# 19_RAM_Memory_module.net
KiCad netlist of a schematic drawn in Altium Designer
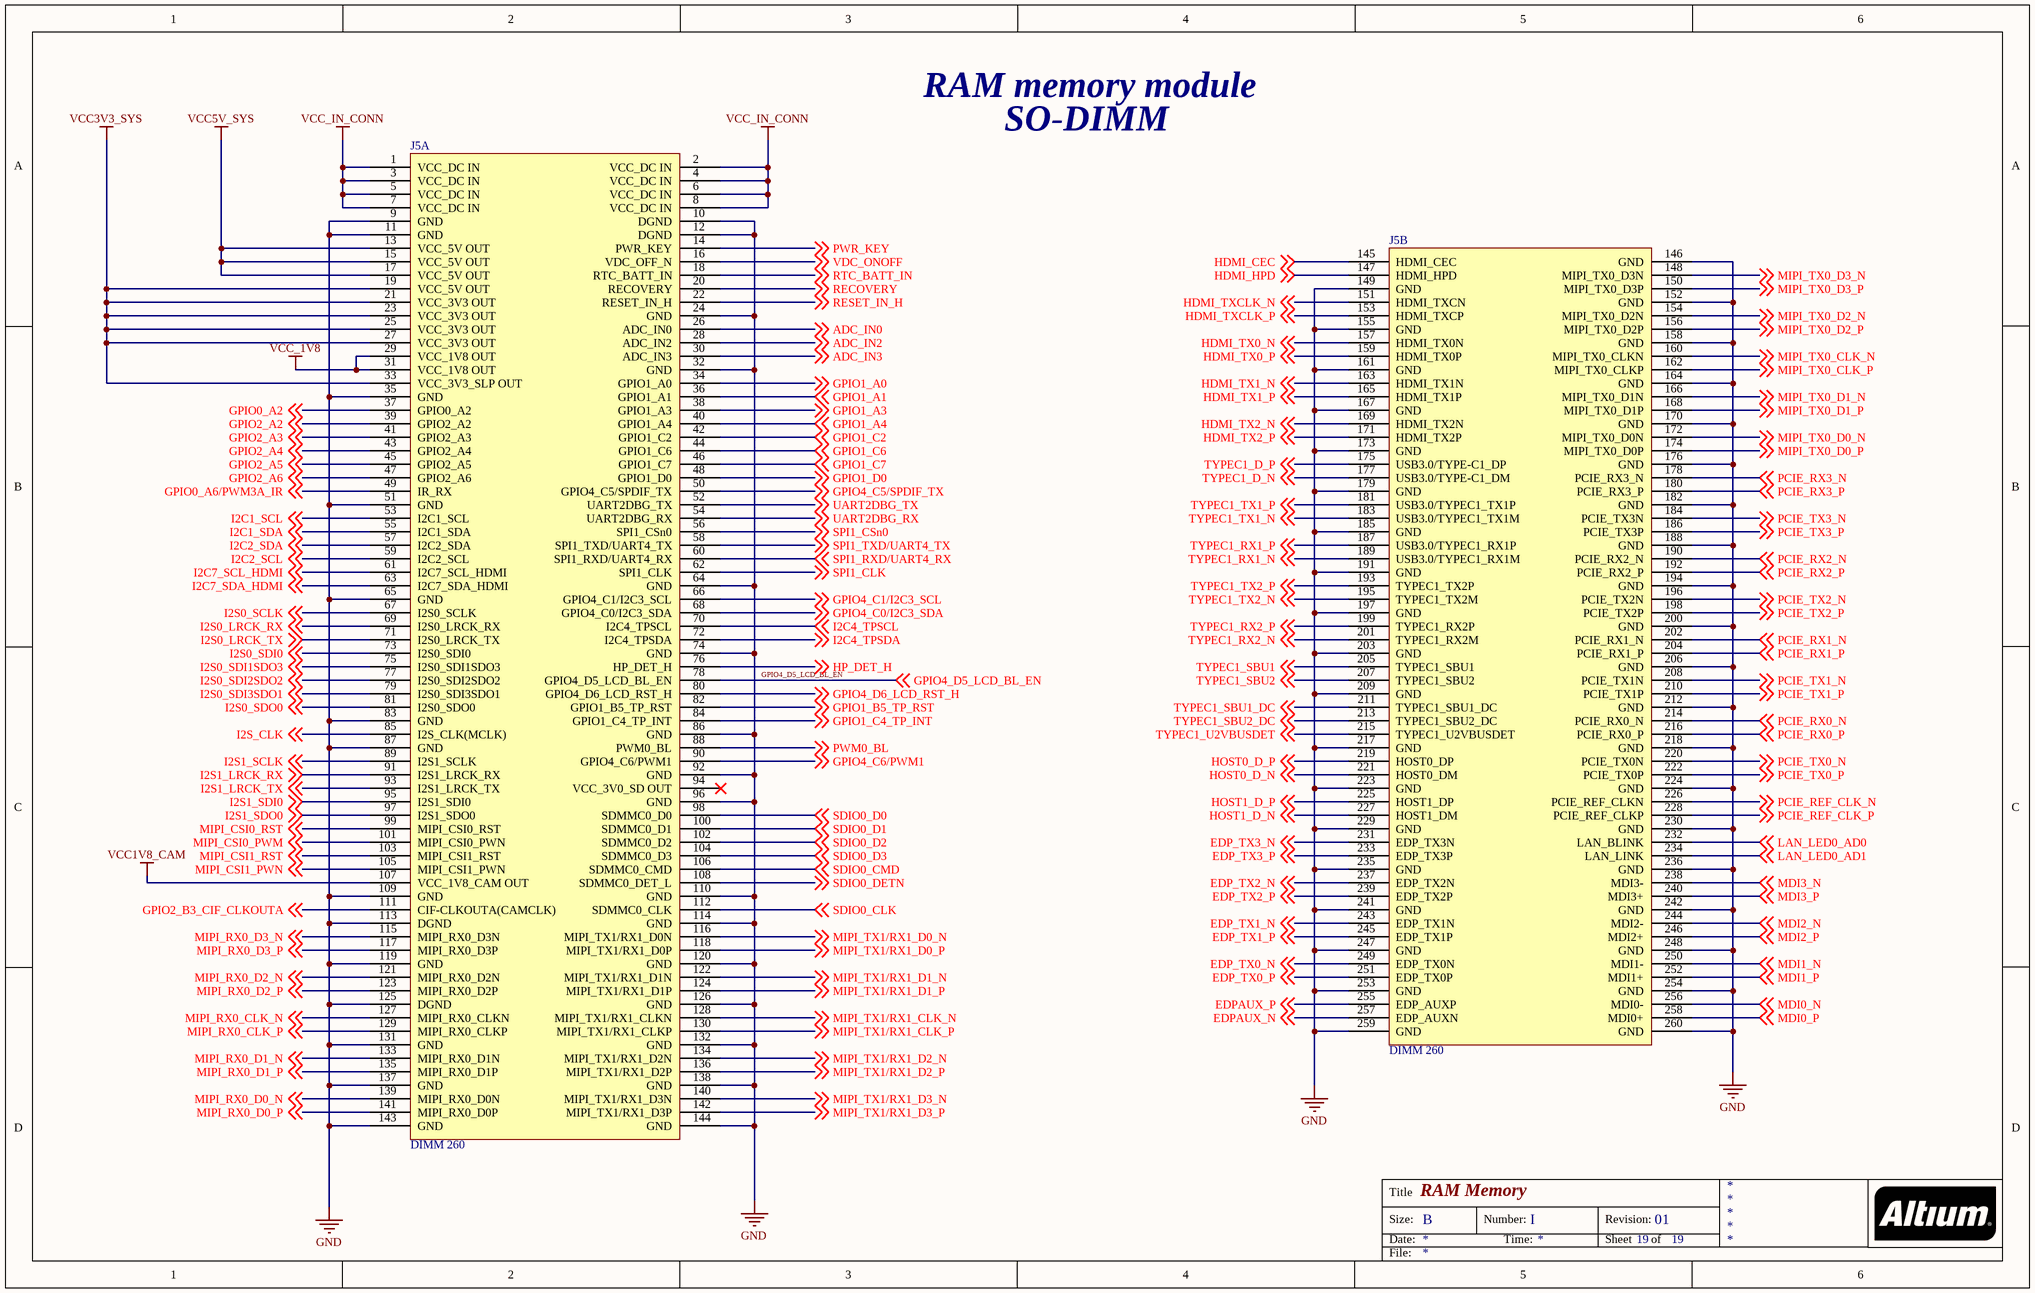
[diagram p0: [19] RAM Memory module.SchDoc]

(export (version "E")
  (design (tool "Eeschema 10.0.6"))
  (components
    (comp (ref "J5")
      (value "DIMM 260")
      (footprint "DIMM260_DDR4")
      (description "Dimm 260 pin smd plating on pcb")
      (fields (field (name "MANUFACTURER") "NA"))
      (libsource (lib "EsteemPCB_SOM_Course_intlib") (part "CON-DIMM_260-SMD"))
    )
  )
  (nets
    (net (code "1") (name "ADC_IN0") (class "Default")
      (node (ref "J5") (pin "26") (pinfunction "ADC_IN0_26") (pintype "passive"))
    )
    (net (code "2") (name "ADC_IN2") (class "Default")
      (node (ref "J5") (pin "28") (pinfunction "ADC_IN2_28") (pintype "passive"))
    )
    (net (code "3") (name "ADC_IN3") (class "Default")
      (node (ref "J5") (pin "30") (pinfunction "ADC_IN3_30") (pintype "passive"))
    )
    (net (code "4") (name "EDPAUX_N") (class "Default")
      (node (ref "J5") (pin "257") (pinfunction "EDP_AUXN_257") (pintype "passive"))
    )
    (net (code "5") (name "EDPAUX_P") (class "Default")
      (node (ref "J5") (pin "255") (pinfunction "EDP_AUXP_255") (pintype "passive"))
    )
    (net (code "6") (name "EDP_TX0_N") (class "Default")
      (node (ref "J5") (pin "249") (pinfunction "EDP_TX0N_249") (pintype "passive"))
    )
    (net (code "7") (name "EDP_TX0_P") (class "Default")
      (node (ref "J5") (pin "251") (pinfunction "EDP_TX0P_251") (pintype "passive"))
    )
    (net (code "8") (name "EDP_TX1_N") (class "Default")
      (node (ref "J5") (pin "243") (pinfunction "EDP_TX1N_243") (pintype "passive"))
    )
    (net (code "9") (name "EDP_TX1_P") (class "Default")
      (node (ref "J5") (pin "245") (pinfunction "EDP_TX1P_245") (pintype "passive"))
    )
    (net (code "10") (name "EDP_TX2_N") (class "Default")
      (node (ref "J5") (pin "237") (pinfunction "EDP_TX2N_237") (pintype "passive"))
    )
    (net (code "11") (name "EDP_TX2_P") (class "Default")
      (node (ref "J5") (pin "239") (pinfunction "EDP_TX2P_239") (pintype "passive"))
    )
    (net (code "12") (name "EDP_TX3_N") (class "Default")
      (node (ref "J5") (pin "231") (pinfunction "EDP_TX3N_231") (pintype "passive"))
    )
    (net (code "13") (name "EDP_TX3_P") (class "Default")
      (node (ref "J5") (pin "233") (pinfunction "EDP_TX3P_233") (pintype "passive"))
    )
    (net (code "14") (name "GND") (class "Default")
      (node (ref "J5") (pin "10") (pinfunction "DGND_10") (pintype "passive"))
      (node (ref "J5") (pin "109") (pinfunction "GND_109") (pintype "passive"))
      (node (ref "J5") (pin "11") (pinfunction "GND_11") (pintype "passive"))
      (node (ref "J5") (pin "110") (pinfunction "GND_110") (pintype "passive"))
      (node (ref "J5") (pin "113") (pinfunction "DGND_113") (pintype "passive"))
      (node (ref "J5") (pin "114") (pinfunction "GND_114") (pintype "passive"))
      (node (ref "J5") (pin "119") (pinfunction "GND_119") (pintype "passive"))
      (node (ref "J5") (pin "12") (pinfunction "DGND_12") (pintype "passive"))
      (node (ref "J5") (pin "120") (pinfunction "GND_120") (pintype "passive"))
      (node (ref "J5") (pin "125") (pinfunction "DGND_125") (pintype "passive"))
      (node (ref "J5") (pin "126") (pinfunction "GND_126") (pintype "passive"))
      (node (ref "J5") (pin "131") (pinfunction "GND_131") (pintype "passive"))
      (node (ref "J5") (pin "132") (pinfunction "GND_132") (pintype "passive"))
      (node (ref "J5") (pin "137") (pinfunction "GND_137") (pintype "passive"))
      (node (ref "J5") (pin "138") (pinfunction "GND_138") (pintype "passive"))
      (node (ref "J5") (pin "143") (pinfunction "GND_143") (pintype "passive"))
      (node (ref "J5") (pin "144") (pinfunction "GND_144") (pintype "passive"))
      (node (ref "J5") (pin "146") (pinfunction "GND_146") (pintype "passive"))
      (node (ref "J5") (pin "149") (pinfunction "GND_149") (pintype "passive"))
      (node (ref "J5") (pin "152") (pinfunction "GND_152") (pintype "passive"))
      (node (ref "J5") (pin "155") (pinfunction "GND_155") (pintype "passive"))
      (node (ref "J5") (pin "158") (pinfunction "GND_158") (pintype "passive"))
      (node (ref "J5") (pin "161") (pinfunction "GND_161") (pintype "passive"))
      (node (ref "J5") (pin "164") (pinfunction "GND_164") (pintype "passive"))
      (node (ref "J5") (pin "167") (pinfunction "GND_167") (pintype "passive"))
      (node (ref "J5") (pin "170") (pinfunction "GND_170") (pintype "passive"))
      (node (ref "J5") (pin "173") (pinfunction "GND_173") (pintype "passive"))
      (node (ref "J5") (pin "176") (pinfunction "GND_176") (pintype "passive"))
      (node (ref "J5") (pin "179") (pinfunction "GND_179") (pintype "passive"))
      (node (ref "J5") (pin "182") (pinfunction "GND_182") (pintype "passive"))
      (node (ref "J5") (pin "185") (pinfunction "GND_185") (pintype "passive"))
      (node (ref "J5") (pin "188") (pinfunction "GND_188") (pintype "passive"))
      (node (ref "J5") (pin "191") (pinfunction "GND_191") (pintype "passive"))
      (node (ref "J5") (pin "194") (pinfunction "GND_194") (pintype "passive"))
      (node (ref "J5") (pin "197") (pinfunction "GND_197") (pintype "passive"))
      (node (ref "J5") (pin "200") (pinfunction "GND_200") (pintype "passive"))
      (node (ref "J5") (pin "203") (pinfunction "GND_203") (pintype "passive"))
      (node (ref "J5") (pin "206") (pinfunction "GND_206") (pintype "passive"))
      (node (ref "J5") (pin "209") (pinfunction "GND_209") (pintype "passive"))
      (node (ref "J5") (pin "212") (pinfunction "GND_212") (pintype "passive"))
      (node (ref "J5") (pin "217") (pinfunction "GND_217") (pintype "passive"))
      (node (ref "J5") (pin "218") (pinfunction "GND_218") (pintype "passive"))
      (node (ref "J5") (pin "223") (pinfunction "GND_223") (pintype "passive"))
      (node (ref "J5") (pin "224") (pinfunction "GND_224") (pintype "passive"))
      (node (ref "J5") (pin "229") (pinfunction "GND_229") (pintype "passive"))
      (node (ref "J5") (pin "230") (pinfunction "GND_230") (pintype "passive"))
      (node (ref "J5") (pin "235") (pinfunction "GND_235") (pintype "passive"))
      (node (ref "J5") (pin "236") (pinfunction "GND_236") (pintype "passive"))
      (node (ref "J5") (pin "24") (pinfunction "GND_24") (pintype "passive"))
      (node (ref "J5") (pin "241") (pinfunction "GND_241") (pintype "passive"))
      (node (ref "J5") (pin "242") (pinfunction "GND_242") (pintype "passive"))
      (node (ref "J5") (pin "247") (pinfunction "GND_247") (pintype "passive"))
      (node (ref "J5") (pin "248") (pinfunction "GND_248") (pintype "passive"))
      (node (ref "J5") (pin "253") (pinfunction "GND_253") (pintype "passive"))
      (node (ref "J5") (pin "254") (pinfunction "GND_254") (pintype "passive"))
      (node (ref "J5") (pin "259") (pinfunction "GND_259") (pintype "passive"))
      (node (ref "J5") (pin "260") (pinfunction "GND_260") (pintype "passive"))
      (node (ref "J5") (pin "32") (pinfunction "GND_32") (pintype "passive"))
      (node (ref "J5") (pin "35") (pinfunction "GND_35") (pintype "passive"))
      (node (ref "J5") (pin "51") (pinfunction "GND_51") (pintype "passive"))
      (node (ref "J5") (pin "64") (pinfunction "GND_64") (pintype "passive"))
      (node (ref "J5") (pin "65") (pinfunction "GND_65") (pintype "passive"))
      (node (ref "J5") (pin "74") (pinfunction "GND_74") (pintype "passive"))
      (node (ref "J5") (pin "83") (pinfunction "GND_83") (pintype "passive"))
      (node (ref "J5") (pin "86") (pinfunction "GND_86") (pintype "passive"))
      (node (ref "J5") (pin "87") (pinfunction "GND_87") (pintype "passive"))
      (node (ref "J5") (pin "9") (pinfunction "GND_9") (pintype "passive"))
      (node (ref "J5") (pin "92") (pinfunction "GND_92") (pintype "passive"))
      (node (ref "J5") (pin "96") (pinfunction "GND_96") (pintype "passive"))
    )
    (net (code "15") (name "GPIO0_A2") (class "Default")
      (node (ref "J5") (pin "37") (pinfunction "GPIO0_A2_37") (pintype "passive"))
    )
    (net (code "16") (name "GPIO0_A6{slash}PWM3A_IR") (class "Default")
      (node (ref "J5") (pin "49") (pinfunction "IR_RX_49") (pintype "passive"))
    )
    (net (code "17") (name "GPIO1_A0") (class "Default")
      (node (ref "J5") (pin "34") (pinfunction "GPIO1_A0_34") (pintype "passive"))
    )
    (net (code "18") (name "GPIO1_A1") (class "Default")
      (node (ref "J5") (pin "36") (pinfunction "GPIO1_A1_36") (pintype "passive"))
    )
    (net (code "19") (name "GPIO1_A3") (class "Default")
      (node (ref "J5") (pin "38") (pinfunction "GPIO1_A3_38") (pintype "passive"))
    )
    (net (code "20") (name "GPIO1_A4") (class "Default")
      (node (ref "J5") (pin "40") (pinfunction "GPIO1_A4_40") (pintype "passive"))
    )
    (net (code "21") (name "GPIO1_B5_TP_RST") (class "Default")
      (node (ref "J5") (pin "82") (pinfunction "GPIO1_B5_TP_RST_82") (pintype "passive"))
    )
    (net (code "22") (name "GPIO1_C2") (class "Default")
      (node (ref "J5") (pin "42") (pinfunction "GPIO1_C2_42") (pintype "passive"))
    )
    (net (code "23") (name "GPIO1_C4_TP_INT") (class "Default")
      (node (ref "J5") (pin "84") (pinfunction "GPIO1_C4_TP_INT_84") (pintype "passive"))
    )
    (net (code "24") (name "GPIO1_C6") (class "Default")
      (node (ref "J5") (pin "44") (pinfunction "GPIO1_C6_44") (pintype "passive"))
    )
    (net (code "25") (name "GPIO1_C7") (class "Default")
      (node (ref "J5") (pin "46") (pinfunction "GPIO1_C7_46") (pintype "passive"))
    )
    (net (code "26") (name "GPIO1_D0") (class "Default")
      (node (ref "J5") (pin "48") (pinfunction "GPIO1_D0_48") (pintype "passive"))
    )
    (net (code "27") (name "GPIO2_A2") (class "Default")
      (node (ref "J5") (pin "39") (pinfunction "GPIO2_A2_39") (pintype "passive"))
    )
    (net (code "28") (name "GPIO2_A3") (class "Default")
      (node (ref "J5") (pin "41") (pinfunction "GPIO2_A3_41") (pintype "passive"))
    )
    (net (code "29") (name "GPIO2_A4") (class "Default")
      (node (ref "J5") (pin "43") (pinfunction "GPIO2_A4_43") (pintype "passive"))
    )
    (net (code "30") (name "GPIO2_A5") (class "Default")
      (node (ref "J5") (pin "45") (pinfunction "GPIO2_A5_45") (pintype "passive"))
    )
    (net (code "31") (name "GPIO2_A6") (class "Default")
      (node (ref "J5") (pin "47") (pinfunction "GPIO2_A6_47") (pintype "passive"))
    )
    (net (code "32") (name "GPIO2_B3_CIF_CLKOUTA") (class "Default")
      (node (ref "J5") (pin "111") (pinfunction "CIF-CLKOUTA(CAMCLK)_111") (pintype "passive"))
    )
    (net (code "33") (name "GPIO4_C0{slash}I2C3_SDA") (class "Default")
      (node (ref "J5") (pin "68") (pinfunction "GPIO4_C0/I2C3_SDA_68") (pintype "passive"))
    )
    (net (code "34") (name "GPIO4_C1{slash}I2C3_SCL") (class "Default")
      (node (ref "J5") (pin "66") (pinfunction "GPIO4_C1/I2C3_SCL_66") (pintype "passive"))
    )
    (net (code "35") (name "GPIO4_C5{slash}SPDIF_TX") (class "Default")
      (node (ref "J5") (pin "50") (pinfunction "GPIO4_C5/SPDIF_TX_50") (pintype "passive"))
    )
    (net (code "36") (name "GPIO4_C6{slash}PWM1") (class "Default")
      (node (ref "J5") (pin "90") (pinfunction "GPIO4_C6/PWM1_90") (pintype "passive"))
    )
    (net (code "37") (name "GPIO4_D5_LCD_BL_EN") (class "Default")
      (node (ref "J5") (pin "78") (pinfunction "GPIO4_D5_LCD_BL_EN_78") (pintype "passive"))
    )
    (net (code "38") (name "GPIO4_D6_LCD_RST_H") (class "Default")
      (node (ref "J5") (pin "80") (pinfunction "GPIO4_D6_LCD_RST_H_80") (pintype "passive"))
    )
    (net (code "39") (name "HDMI_CEC") (class "Default")
      (node (ref "J5") (pin "145") (pinfunction "HDMI_CEC_145") (pintype "passive"))
    )
    (net (code "40") (name "HDMI_HPD") (class "Default")
      (node (ref "J5") (pin "147") (pinfunction "HDMI_HPD_147") (pintype "passive"))
    )
    (net (code "41") (name "HDMI_TX0_N") (class "Default")
      (node (ref "J5") (pin "157") (pinfunction "HDMI_TX0N_157") (pintype "passive"))
    )
    (net (code "42") (name "HDMI_TX0_P") (class "Default")
      (node (ref "J5") (pin "159") (pinfunction "HDMI_TX0P_159") (pintype "passive"))
    )
    (net (code "43") (name "HDMI_TX1_N") (class "Default")
      (node (ref "J5") (pin "163") (pinfunction "HDMI_TX1N_163") (pintype "passive"))
    )
    (net (code "44") (name "HDMI_TX1_P") (class "Default")
      (node (ref "J5") (pin "165") (pinfunction "HDMI_TX1P_165") (pintype "passive"))
    )
    (net (code "45") (name "HDMI_TX2_N") (class "Default")
      (node (ref "J5") (pin "169") (pinfunction "HDMI_TX2N_169") (pintype "passive"))
    )
    (net (code "46") (name "HDMI_TX2_P") (class "Default")
      (node (ref "J5") (pin "171") (pinfunction "HDMI_TX2P_171") (pintype "passive"))
    )
    (net (code "47") (name "HDMI_TXCLK_N") (class "Default")
      (node (ref "J5") (pin "151") (pinfunction "HDMI_TXCN_151") (pintype "passive"))
    )
    (net (code "48") (name "HDMI_TXCLK_P") (class "Default")
      (node (ref "J5") (pin "153") (pinfunction "HDMI_TXCP_153") (pintype "passive"))
    )
    (net (code "49") (name "HOST0_D_N") (class "Default")
      (node (ref "J5") (pin "221") (pinfunction "HOST0_DM_221") (pintype "passive"))
    )
    (net (code "50") (name "HOST0_D_P") (class "Default")
      (node (ref "J5") (pin "219") (pinfunction "HOST0_DP_219") (pintype "passive"))
    )
    (net (code "51") (name "HOST1_D_N") (class "Default")
      (node (ref "J5") (pin "227") (pinfunction "HOST1_DM_227") (pintype "passive"))
    )
    (net (code "52") (name "HOST1_D_P") (class "Default")
      (node (ref "J5") (pin "225") (pinfunction "HOST1_DP_225") (pintype "passive"))
    )
    (net (code "53") (name "HP_DET_H") (class "Default")
      (node (ref "J5") (pin "76") (pinfunction "HP_DET_H_76") (pintype "passive"))
    )
    (net (code "54") (name "I2C1_SCL") (class "Default")
      (node (ref "J5") (pin "53") (pinfunction "I2C1_SCL_53") (pintype "passive"))
    )
    (net (code "55") (name "I2C1_SDA") (class "Default")
      (node (ref "J5") (pin "55") (pinfunction "I2C1_SDA_55") (pintype "passive"))
    )
    (net (code "56") (name "I2C2_SCL") (class "Default")
      (node (ref "J5") (pin "59") (pinfunction "I2C2_SCL_59") (pintype "passive"))
    )
    (net (code "57") (name "I2C2_SDA") (class "Default")
      (node (ref "J5") (pin "57") (pinfunction "I2C2_SDA_57") (pintype "passive"))
    )
    (net (code "58") (name "I2C4_TPSCL") (class "Default")
      (node (ref "J5") (pin "70") (pinfunction "I2C4_TPSCL_70") (pintype "passive"))
    )
    (net (code "59") (name "I2C4_TPSDA") (class "Default")
      (node (ref "J5") (pin "72") (pinfunction "I2C4_TPSDA_72") (pintype "passive"))
    )
    (net (code "60") (name "I2C7_SCL_HDMI") (class "Default")
      (node (ref "J5") (pin "61") (pinfunction "I2C7_SCL_HDMI_61") (pintype "passive"))
    )
    (net (code "61") (name "I2C7_SDA_HDMI") (class "Default")
      (node (ref "J5") (pin "63") (pinfunction "I2C7_SDA_HDMI_63") (pintype "passive"))
    )
    (net (code "62") (name "I2S0_LRCK_RX") (class "Default")
      (node (ref "J5") (pin "69") (pinfunction "I2S0_LRCK_RX_69") (pintype "passive"))
    )
    (net (code "63") (name "I2S0_LRCK_TX") (class "Default")
      (node (ref "J5") (pin "71") (pinfunction "I2S0_LRCK_TX_71") (pintype "passive"))
    )
    (net (code "64") (name "I2S0_SCLK") (class "Default")
      (node (ref "J5") (pin "67") (pinfunction "I2S0_SCLK_67") (pintype "passive"))
    )
    (net (code "65") (name "I2S0_SDI0") (class "Default")
      (node (ref "J5") (pin "73") (pinfunction "I2S0_SDI0_73") (pintype "passive"))
    )
    (net (code "66") (name "I2S0_SDI1SDO3") (class "Default")
      (node (ref "J5") (pin "75") (pinfunction "I2S0_SDI1SDO3_75") (pintype "passive"))
    )
    (net (code "67") (name "I2S0_SDI2SDO2") (class "Default")
      (node (ref "J5") (pin "77") (pinfunction "I2S0_SDI2SDO2_77") (pintype "passive"))
    )
    (net (code "68") (name "I2S0_SDI3SDO1") (class "Default")
      (node (ref "J5") (pin "79") (pinfunction "I2S0_SDI3SDO1_79") (pintype "passive"))
    )
    (net (code "69") (name "I2S0_SDO0") (class "Default")
      (node (ref "J5") (pin "81") (pinfunction "I2S0_SDO0_81") (pintype "passive"))
    )
    (net (code "70") (name "I2S1_LRCK_RX") (class "Default")
      (node (ref "J5") (pin "91") (pinfunction "I2S1_LRCK_RX_91") (pintype "passive"))
    )
    (net (code "71") (name "I2S1_LRCK_TX") (class "Default")
      (node (ref "J5") (pin "93") (pinfunction "I2S1_LRCK_TX_93") (pintype "passive"))
    )
    (net (code "72") (name "I2S1_SCLK") (class "Default")
      (node (ref "J5") (pin "89") (pinfunction "I2S1_SCLK_89") (pintype "passive"))
    )
    (net (code "73") (name "I2S1_SDI0") (class "Default")
      (node (ref "J5") (pin "95") (pinfunction "I2S1_SDI0_95") (pintype "passive"))
    )
    (net (code "74") (name "I2S1_SDO0") (class "Default")
      (node (ref "J5") (pin "97") (pinfunction "I2S1_SDO0_97") (pintype "passive"))
    )
    (net (code "75") (name "I2S_CLK") (class "Default")
      (node (ref "J5") (pin "85") (pinfunction "I2S_CLK(MCLK)_85") (pintype "passive"))
    )
    (net (code "76") (name "LAN_LED0_AD0") (class "Default")
      (node (ref "J5") (pin "232") (pinfunction "LAN_BLINK_232") (pintype "passive"))
    )
    (net (code "77") (name "LAN_LED0_AD1") (class "Default")
      (node (ref "J5") (pin "234") (pinfunction "LAN_LINK_234") (pintype "passive"))
    )
    (net (code "78") (name "MDI0_N") (class "Default")
      (node (ref "J5") (pin "256") (pinfunction "MDI0-_256") (pintype "passive"))
    )
    (net (code "79") (name "MDI0_P") (class "Default")
      (node (ref "J5") (pin "258") (pinfunction "MDI0+_258") (pintype "passive"))
    )
    (net (code "80") (name "MDI1_N") (class "Default")
      (node (ref "J5") (pin "250") (pinfunction "MDI1-_250") (pintype "passive"))
    )
    (net (code "81") (name "MDI1_P") (class "Default")
      (node (ref "J5") (pin "252") (pinfunction "MDI1+_252") (pintype "passive"))
    )
    (net (code "82") (name "MDI2_N") (class "Default")
      (node (ref "J5") (pin "244") (pinfunction "MDI2-_244") (pintype "passive"))
    )
    (net (code "83") (name "MDI2_P") (class "Default")
      (node (ref "J5") (pin "246") (pinfunction "MDI2+_246") (pintype "passive"))
    )
    (net (code "84") (name "MDI3_N") (class "Default")
      (node (ref "J5") (pin "238") (pinfunction "MDI3-_238") (pintype "passive"))
    )
    (net (code "85") (name "MDI3_P") (class "Default")
      (node (ref "J5") (pin "240") (pinfunction "MDI3+_240") (pintype "passive"))
    )
    (net (code "86") (name "MIPI_CSI0_PWM") (class "Default")
      (node (ref "J5") (pin "101") (pinfunction "MIPI_CSI0_PWN_101") (pintype "passive"))
    )
    (net (code "87") (name "MIPI_CSI0_RST") (class "Default")
      (node (ref "J5") (pin "99") (pinfunction "MIPI_CSI0_RST_99") (pintype "passive"))
    )
    (net (code "88") (name "MIPI_CSI1_PWN") (class "Default")
      (node (ref "J5") (pin "105") (pinfunction "MIPI_CSI1_PWN_105") (pintype "passive"))
    )
    (net (code "89") (name "MIPI_CSI1_RST") (class "Default")
      (node (ref "J5") (pin "103") (pinfunction "MIPI_CSI1_RST_103") (pintype "passive"))
    )
    (net (code "90") (name "MIPI_RX0_CLK_N") (class "Default")
      (node (ref "J5") (pin "127") (pinfunction "MIPI_RX0_CLKN_127") (pintype "passive"))
    )
    (net (code "91") (name "MIPI_RX0_CLK_P") (class "Default")
      (node (ref "J5") (pin "129") (pinfunction "MIPI_RX0_CLKP_129") (pintype "passive"))
    )
    (net (code "92") (name "MIPI_RX0_D0_N") (class "Default")
      (node (ref "J5") (pin "139") (pinfunction "MIPI_RX0_D0N_139") (pintype "passive"))
    )
    (net (code "93") (name "MIPI_RX0_D0_P") (class "Default")
      (node (ref "J5") (pin "141") (pinfunction "MIPI_RX0_D0P_141") (pintype "passive"))
    )
    (net (code "94") (name "MIPI_RX0_D1_N") (class "Default")
      (node (ref "J5") (pin "133") (pinfunction "MIPI_RX0_D1N_133") (pintype "passive"))
    )
    (net (code "95") (name "MIPI_RX0_D1_P") (class "Default")
      (node (ref "J5") (pin "135") (pinfunction "MIPI_RX0_D1P_135") (pintype "passive"))
    )
    (net (code "96") (name "MIPI_RX0_D2_N") (class "Default")
      (node (ref "J5") (pin "121") (pinfunction "MIPI_RX0_D2N_121") (pintype "passive"))
    )
    (net (code "97") (name "MIPI_RX0_D2_P") (class "Default")
      (node (ref "J5") (pin "123") (pinfunction "MIPI_RX0_D2P_123") (pintype "passive"))
    )
    (net (code "98") (name "MIPI_RX0_D3_N") (class "Default")
      (node (ref "J5") (pin "115") (pinfunction "MIPI_RX0_D3N_115") (pintype "passive"))
    )
    (net (code "99") (name "MIPI_RX0_D3_P") (class "Default")
      (node (ref "J5") (pin "117") (pinfunction "MIPI_RX0_D3P_117") (pintype "passive"))
    )
    (net (code "100") (name "MIPI_TX0_CLK_N") (class "Default")
      (node (ref "J5") (pin "160") (pinfunction "MIPI_TX0_CLKN_160") (pintype "passive"))
    )
    (net (code "101") (name "MIPI_TX0_CLK_P") (class "Default")
      (node (ref "J5") (pin "162") (pinfunction "MIPI_TX0_CLKP_162") (pintype "passive"))
    )
    (net (code "102") (name "MIPI_TX0_D0_N") (class "Default")
      (node (ref "J5") (pin "172") (pinfunction "MIPI_TX0_D0N_172") (pintype "passive"))
    )
    (net (code "103") (name "MIPI_TX0_D0_P") (class "Default")
      (node (ref "J5") (pin "174") (pinfunction "MIPI_TX0_D0P_174") (pintype "passive"))
    )
    (net (code "104") (name "MIPI_TX0_D1_N") (class "Default")
      (node (ref "J5") (pin "166") (pinfunction "MIPI_TX0_D1N_166") (pintype "passive"))
    )
    (net (code "105") (name "MIPI_TX0_D1_P") (class "Default")
      (node (ref "J5") (pin "168") (pinfunction "MIPI_TX0_D1P_168") (pintype "passive"))
    )
    (net (code "106") (name "MIPI_TX0_D2_N") (class "Default")
      (node (ref "J5") (pin "154") (pinfunction "MIPI_TX0_D2N_154") (pintype "passive"))
    )
    (net (code "107") (name "MIPI_TX0_D2_P") (class "Default")
      (node (ref "J5") (pin "156") (pinfunction "MIPI_TX0_D2P_156") (pintype "passive"))
    )
    (net (code "108") (name "MIPI_TX0_D3_N") (class "Default")
      (node (ref "J5") (pin "148") (pinfunction "MIPI_TX0_D3N_148") (pintype "passive"))
    )
    (net (code "109") (name "MIPI_TX0_D3_P") (class "Default")
      (node (ref "J5") (pin "150") (pinfunction "MIPI_TX0_D3P_150") (pintype "passive"))
    )
    (net (code "110") (name "MIPI_TX1{slash}RX1_CLK_N") (class "Default")
      (node (ref "J5") (pin "128") (pinfunction "MIPI_TX1/RX1_CLKN_128") (pintype "passive"))
    )
    (net (code "111") (name "MIPI_TX1{slash}RX1_CLK_P") (class "Default")
      (node (ref "J5") (pin "130") (pinfunction "MIPI_TX1/RX1_CLKP_130") (pintype "passive"))
    )
    (net (code "112") (name "MIPI_TX1{slash}RX1_D0_N") (class "Default")
      (node (ref "J5") (pin "116") (pinfunction "MIPI_TX1/RX1_D0N_116") (pintype "passive"))
    )
    (net (code "113") (name "MIPI_TX1{slash}RX1_D0_P") (class "Default")
      (node (ref "J5") (pin "118") (pinfunction "MIPI_TX1/RX1_D0P_118") (pintype "passive"))
    )
    (net (code "114") (name "MIPI_TX1{slash}RX1_D1_N") (class "Default")
      (node (ref "J5") (pin "122") (pinfunction "MIPI_TX1/RX1_D1N_122") (pintype "passive"))
    )
    (net (code "115") (name "MIPI_TX1{slash}RX1_D1_P") (class "Default")
      (node (ref "J5") (pin "124") (pinfunction "MIPI_TX1/RX1_D1P_124") (pintype "passive"))
    )
    (net (code "116") (name "MIPI_TX1{slash}RX1_D2_N") (class "Default")
      (node (ref "J5") (pin "134") (pinfunction "MIPI_TX1/RX1_D2N_134") (pintype "passive"))
    )
    (net (code "117") (name "MIPI_TX1{slash}RX1_D2_P") (class "Default")
      (node (ref "J5") (pin "136") (pinfunction "MIPI_TX1/RX1_D2P_136") (pintype "passive"))
    )
    (net (code "118") (name "MIPI_TX1{slash}RX1_D3_N") (class "Default")
      (node (ref "J5") (pin "140") (pinfunction "MIPI_TX1/RX1_D3N_140") (pintype "passive"))
    )
    (net (code "119") (name "MIPI_TX1{slash}RX1_D3_P") (class "Default")
      (node (ref "J5") (pin "142") (pinfunction "MIPI_TX1/RX1_D3P_142") (pintype "passive"))
    )
    (net (code "120") (name "PCIE_REF_CLK_N") (class "Default")
      (node (ref "J5") (pin "226") (pinfunction "PCIE_REF_CLKN_226") (pintype "passive"))
    )
    (net (code "121") (name "PCIE_REF_CLK_P") (class "Default")
      (node (ref "J5") (pin "228") (pinfunction "PCIE_REF_CLKP_228") (pintype "passive"))
    )
    (net (code "122") (name "PCIE_RX0_N") (class "Default")
      (node (ref "J5") (pin "214") (pinfunction "PCIE_RX0_N_214") (pintype "passive"))
    )
    (net (code "123") (name "PCIE_RX0_P") (class "Default")
      (node (ref "J5") (pin "216") (pinfunction "PCIE_RX0_P_216") (pintype "passive"))
    )
    (net (code "124") (name "PCIE_RX1_N") (class "Default")
      (node (ref "J5") (pin "202") (pinfunction "PCIE_RX1_N_202") (pintype "passive"))
    )
    (net (code "125") (name "PCIE_RX1_P") (class "Default")
      (node (ref "J5") (pin "204") (pinfunction "PCIE_RX1_P_204") (pintype "passive"))
    )
    (net (code "126") (name "PCIE_RX2_N") (class "Default")
      (node (ref "J5") (pin "190") (pinfunction "PCIE_RX2_N_190") (pintype "passive"))
    )
    (net (code "127") (name "PCIE_RX2_P") (class "Default")
      (node (ref "J5") (pin "192") (pinfunction "PCIE_RX2_P_192") (pintype "passive"))
    )
    (net (code "128") (name "PCIE_RX3_N") (class "Default")
      (node (ref "J5") (pin "178") (pinfunction "PCIE_RX3_N_178") (pintype "passive"))
    )
    (net (code "129") (name "PCIE_RX3_P") (class "Default")
      (node (ref "J5") (pin "180") (pinfunction "PCIE_RX3_P_180") (pintype "passive"))
    )
    (net (code "130") (name "PCIE_TX0_N") (class "Default")
      (node (ref "J5") (pin "220") (pinfunction "PCIE_TX0N_220") (pintype "passive"))
    )
    (net (code "131") (name "PCIE_TX0_P") (class "Default")
      (node (ref "J5") (pin "222") (pinfunction "PCIE_TX0P_222") (pintype "passive"))
    )
    (net (code "132") (name "PCIE_TX1_N") (class "Default")
      (node (ref "J5") (pin "208") (pinfunction "PCIE_TX1N_208") (pintype "passive"))
    )
    (net (code "133") (name "PCIE_TX1_P") (class "Default")
      (node (ref "J5") (pin "210") (pinfunction "PCIE_TX1P_210") (pintype "passive"))
    )
    (net (code "134") (name "PCIE_TX2_N") (class "Default")
      (node (ref "J5") (pin "196") (pinfunction "PCIE_TX2N_196") (pintype "passive"))
    )
    (net (code "135") (name "PCIE_TX2_P") (class "Default")
      (node (ref "J5") (pin "198") (pinfunction "PCIE_TX2P_198") (pintype "passive"))
    )
    (net (code "136") (name "PCIE_TX3_N") (class "Default")
      (node (ref "J5") (pin "184") (pinfunction "PCIE_TX3N_184") (pintype "passive"))
    )
    (net (code "137") (name "PCIE_TX3_P") (class "Default")
      (node (ref "J5") (pin "186") (pinfunction "PCIE_TX3P_186") (pintype "passive"))
    )
    (net (code "138") (name "PWM0_BL") (class "Default")
      (node (ref "J5") (pin "88") (pinfunction "PWM0_BL_88") (pintype "passive"))
    )
    (net (code "139") (name "PWR_KEY") (class "Default")
      (node (ref "J5") (pin "14") (pinfunction "PWR_KEY_14") (pintype "passive"))
    )
    (net (code "140") (name "RECOVERY") (class "Default")
      (node (ref "J5") (pin "20") (pinfunction "RECOVERY_20") (pintype "passive"))
    )
    (net (code "141") (name "RESET_IN_H") (class "Default")
      (node (ref "J5") (pin "22") (pinfunction "RESET_IN_H_22") (pintype "passive"))
    )
    (net (code "142") (name "RTC_BATT_IN") (class "Default")
      (node (ref "J5") (pin "18") (pinfunction "RTC_BATT_IN_18") (pintype "passive"))
    )
    (net (code "143") (name "SDIO0_CLK") (class "Default")
      (node (ref "J5") (pin "112") (pinfunction "SDMMC0_CLK_112") (pintype "passive"))
    )
    (net (code "144") (name "SDIO0_CMD") (class "Default")
      (node (ref "J5") (pin "106") (pinfunction "SDMMC0_CMD_106") (pintype "passive"))
    )
    (net (code "145") (name "SDIO0_D0") (class "Default")
      (node (ref "J5") (pin "98") (pinfunction "SDMMC0_D0_98") (pintype "passive"))
    )
    (net (code "146") (name "SDIO0_D1") (class "Default")
      (node (ref "J5") (pin "100") (pinfunction "SDMMC0_D1_100") (pintype "passive"))
    )
    (net (code "147") (name "SDIO0_D2") (class "Default")
      (node (ref "J5") (pin "102") (pinfunction "SDMMC0_D2_102") (pintype "passive"))
    )
    (net (code "148") (name "SDIO0_D3") (class "Default")
      (node (ref "J5") (pin "104") (pinfunction "SDMMC0_D3_104") (pintype "passive"))
    )
    (net (code "149") (name "SDIO0_DETN") (class "Default")
      (node (ref "J5") (pin "108") (pinfunction "SDMMC0_DET_L_108") (pintype "passive"))
    )
    (net (code "150") (name "SPI1_CLK") (class "Default")
      (node (ref "J5") (pin "62") (pinfunction "SPI1_CLK_62") (pintype "passive"))
    )
    (net (code "151") (name "SPI1_CSn0") (class "Default")
      (node (ref "J5") (pin "56") (pinfunction "SPI1_CSn0_56") (pintype "passive"))
    )
    (net (code "152") (name "SPI1_RXD{slash}UART4_RX") (class "Default")
      (node (ref "J5") (pin "60") (pinfunction "SPI1_RXD/UART4_RX_60") (pintype "passive"))
    )
    (net (code "153") (name "SPI1_TXD{slash}UART4_TX") (class "Default")
      (node (ref "J5") (pin "58") (pinfunction "SPI1_TXD/UART4_TX_58") (pintype "passive"))
    )
    (net (code "154") (name "TYPEC1_D_N") (class "Default")
      (node (ref "J5") (pin "177") (pinfunction "USB3.0/TYPE-C1_DM_177") (pintype "passive"))
    )
    (net (code "155") (name "TYPEC1_D_P") (class "Default")
      (node (ref "J5") (pin "175") (pinfunction "USB3.0/TYPE-C1_DP_175") (pintype "passive"))
    )
    (net (code "156") (name "TYPEC1_RX1_N") (class "Default")
      (node (ref "J5") (pin "189") (pinfunction "USB3.0/TYPEC1_RX1M_189") (pintype "passive"))
    )
    (net (code "157") (name "TYPEC1_RX1_P") (class "Default")
      (node (ref "J5") (pin "187") (pinfunction "USB3.0/TYPEC1_RX1P_187") (pintype "passive"))
    )
    (net (code "158") (name "TYPEC1_RX2_N") (class "Default")
      (node (ref "J5") (pin "201") (pinfunction "TYPEC1_RX2M_201") (pintype "passive"))
    )
    (net (code "159") (name "TYPEC1_RX2_P") (class "Default")
      (node (ref "J5") (pin "199") (pinfunction "TYPEC1_RX2P_199") (pintype "passive"))
    )
    (net (code "160") (name "TYPEC1_SBU1") (class "Default")
      (node (ref "J5") (pin "205") (pinfunction "TYPEC1_SBU1_205") (pintype "passive"))
    )
    (net (code "161") (name "TYPEC1_SBU1_DC") (class "Default")
      (node (ref "J5") (pin "211") (pinfunction "TYPEC1_SBU1_DC_211") (pintype "passive"))
    )
    (net (code "162") (name "TYPEC1_SBU2") (class "Default")
      (node (ref "J5") (pin "207") (pinfunction "TYPEC1_SBU2_207") (pintype "passive"))
    )
    (net (code "163") (name "TYPEC1_SBU2_DC") (class "Default")
      (node (ref "J5") (pin "213") (pinfunction "TYPEC1_SBU2_DC_213") (pintype "passive"))
    )
    (net (code "164") (name "TYPEC1_TX1_N") (class "Default")
      (node (ref "J5") (pin "183") (pinfunction "USB3.0/TYPEC1_TX1M_183") (pintype "passive"))
    )
    (net (code "165") (name "TYPEC1_TX1_P") (class "Default")
      (node (ref "J5") (pin "181") (pinfunction "USB3.0/TYPEC1_TX1P_181") (pintype "passive"))
    )
    (net (code "166") (name "TYPEC1_TX2_N") (class "Default")
      (node (ref "J5") (pin "195") (pinfunction "TYPEC1_TX2M_195") (pintype "passive"))
    )
    (net (code "167") (name "TYPEC1_TX2_P") (class "Default")
      (node (ref "J5") (pin "193") (pinfunction "TYPEC1_TX2P_193") (pintype "passive"))
    )
    (net (code "168") (name "TYPEC1_U2VBUSDET") (class "Default")
      (node (ref "J5") (pin "215") (pinfunction "TYPEC1_U2VBUSDET_215") (pintype "passive"))
    )
    (net (code "169") (name "UART2DBG_RX") (class "Default")
      (node (ref "J5") (pin "54") (pinfunction "UART2DBG_RX_54") (pintype "passive"))
    )
    (net (code "170") (name "UART2DBG_TX") (class "Default")
      (node (ref "J5") (pin "52") (pinfunction "UART2DBG_TX_52") (pintype "passive"))
    )
    (net (code "171") (name "VCC1V8_CAM") (class "Default")
      (node (ref "J5") (pin "107") (pinfunction "VCC_1V8_CAM_OUT_107") (pintype "passive"))
    )
    (net (code "172") (name "VCC3V3_SYS") (class "Default")
      (node (ref "J5") (pin "19") (pinfunction "VCC_5V_OUT_19") (pintype "passive"))
      (node (ref "J5") (pin "21") (pinfunction "VCC_3V3_OUT_21") (pintype "passive"))
      (node (ref "J5") (pin "23") (pinfunction "VCC_3V3_OUT_23") (pintype "passive"))
      (node (ref "J5") (pin "25") (pinfunction "VCC_3V3_OUT_25") (pintype "passive"))
      (node (ref "J5") (pin "27") (pinfunction "VCC_3V3_OUT_27") (pintype "passive"))
      (node (ref "J5") (pin "33") (pinfunction "VCC_3V3_SLP_OUT_33") (pintype "passive"))
    )
    (net (code "173") (name "VCC5V_SYS") (class "Default")
      (node (ref "J5") (pin "13") (pinfunction "VCC_5V_OUT_13") (pintype "passive"))
      (node (ref "J5") (pin "15") (pinfunction "VCC_5V_OUT_15") (pintype "passive"))
      (node (ref "J5") (pin "17") (pinfunction "VCC_5V_OUT_17") (pintype "passive"))
    )
    (net (code "174") (name "VCC_1V8") (class "Default")
      (node (ref "J5") (pin "29") (pinfunction "VCC_1V8_OUT_29") (pintype "passive"))
      (node (ref "J5") (pin "31") (pinfunction "VCC_1V8_OUT_31") (pintype "passive"))
    )
    (net (code "175") (name "VCC_IN_CONN") (class "Default")
      (node (ref "J5") (pin "1") (pinfunction "VCC_DC_IN_1") (pintype "passive"))
      (node (ref "J5") (pin "2") (pinfunction "VCC_DC_IN_2") (pintype "passive"))
      (node (ref "J5") (pin "3") (pinfunction "VCC_DC_IN_3") (pintype "passive"))
      (node (ref "J5") (pin "4") (pinfunction "VCC_DC_IN_4") (pintype "passive"))
      (node (ref "J5") (pin "5") (pinfunction "VCC_DC_IN_5") (pintype "passive"))
      (node (ref "J5") (pin "6") (pinfunction "VCC_DC_IN_6") (pintype "passive"))
      (node (ref "J5") (pin "7") (pinfunction "VCC_DC_IN_7") (pintype "passive"))
      (node (ref "J5") (pin "8") (pinfunction "VCC_DC_IN_8") (pintype "passive"))
    )
    (net (code "176") (name "VDC_ONOFF") (class "Default")
      (node (ref "J5") (pin "16") (pinfunction "VDC_OFF_N_16") (pintype "passive"))
    )
    (net (code "177") (name "unconnected-(J5A-VCC_3V0_SD_OUT-Pad94)") (class "Default")
      (node (ref "J5") (pin "94") (pinfunction "VCC_3V0_SD_OUT_94") (pintype "passive+no_connect"))
    )
  )
)
